# basketball_robot_connection_strip_2018.net
KiCad netlist of a schematic drawn in Altium Designer
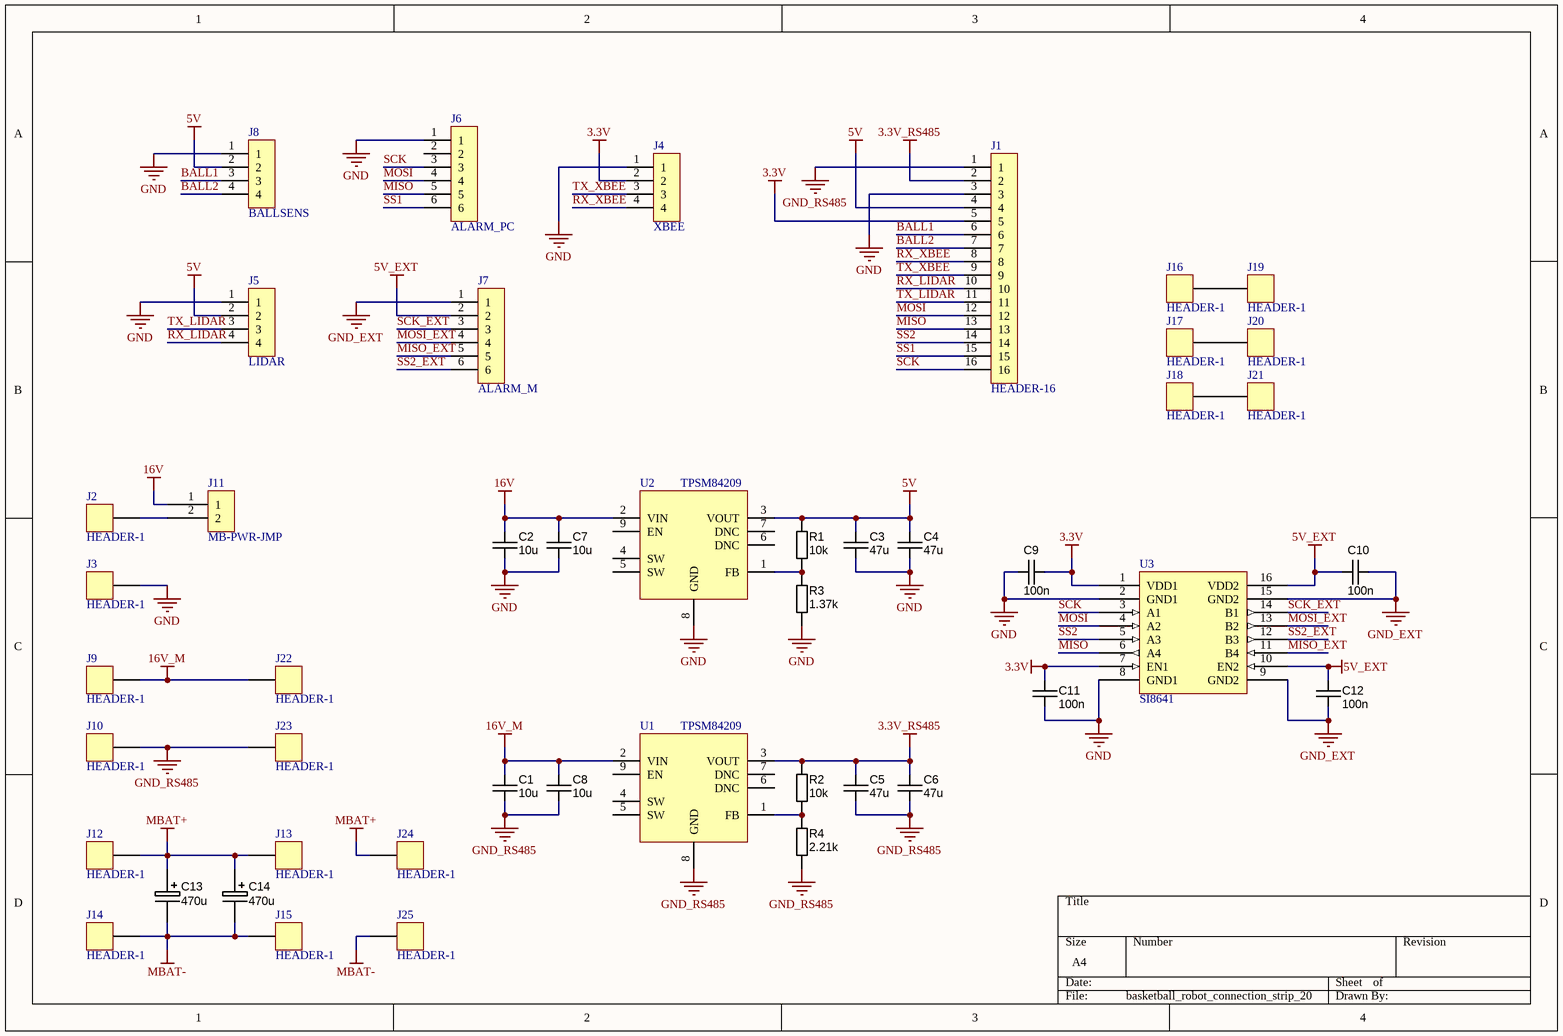
[diagram p0: basketball_robot_connection_strip_2018.SchDoc]

(export (version "E")
  (design (tool "Eeschema 10.0.6"))
  (components
    (comp (ref "C1")
      (value "10u")
      (footprint "CAPC3216X180N")
      (description "Capacitor SMD Cer 10uF 10% 10V X5R 1206")
      (fields (field (name "TOLERANCE") "±10%"))
      (libsource (lib "PBL - Capacitors") (part "CAPC_10u_1206_10V"))
    )
    (comp (ref "C2")
      (value "10u")
      (footprint "CAPC3216X180N")
      (description "Capacitor SMD Cer 10uF 10% 10V X5R 1206")
      (fields (field (name "TOLERANCE") "±10%"))
      (libsource (lib "PBL - Capacitors") (part "CAPC_10u_1206_10V"))
    )
    (comp (ref "C3")
      (value "47u")
      (footprint "CAPC3216X180N")
      (description "Capacitor SMD Cer 10uF 10% 10V X5R 1206")
      (fields (field (name "TOLERANCE") "±10%"))
      (libsource (lib "PBL - Capacitors") (part "CAPC_10u_1206_10V"))
    )
    (comp (ref "C4")
      (value "47u")
      (footprint "CAPC3216X180N")
      (description "Capacitor SMD Cer 10uF 10% 10V X5R 1206")
      (fields (field (name "TOLERANCE") "±10%"))
      (libsource (lib "PBL - Capacitors") (part "CAPC_10u_1206_10V"))
    )
    (comp (ref "C5")
      (value "47u")
      (footprint "CAPC3216X180N")
      (description "Capacitor SMD Cer 10uF 10% 10V X5R 1206")
      (fields (field (name "TOLERANCE") "±10%"))
      (libsource (lib "PBL - Capacitors") (part "CAPC_10u_1206_10V"))
    )
    (comp (ref "C6")
      (value "47u")
      (footprint "CAPC3216X180N")
      (description "Capacitor SMD Cer 10uF 10% 10V X5R 1206")
      (fields (field (name "TOLERANCE") "±10%"))
      (libsource (lib "PBL - Capacitors") (part "CAPC_10u_1206_10V"))
    )
    (comp (ref "C7")
      (value "10u")
      (footprint "CAPC3216X180N")
      (description "Capacitor SMD Cer 10uF 10% 10V X5R 1206")
      (fields (field (name "TOLERANCE") "±10%"))
      (libsource (lib "PBL - Capacitors") (part "CAPC_10u_1206_10V"))
    )
    (comp (ref "C8")
      (value "10u")
      (footprint "CAPC3216X180N")
      (description "Capacitor SMD Cer 10uF 10% 10V X5R 1206")
      (fields (field (name "TOLERANCE") "±10%"))
      (libsource (lib "PBL - Capacitors") (part "CAPC_10u_1206_10V"))
    )
    (comp (ref "C9")
      (value "100n")
      (footprint "CAPC1608X90N")
      (description "Capacitor SMD Cer 100nF 10% 50V X7R 0603")
      (fields (field (name "TOLERANCE") "±10%"))
      (libsource (lib "PBL - Capacitors") (part "CAPC_100n_0603_X7R_50V_10%"))
    )
    (comp (ref "C10")
      (value "100n")
      (footprint "CAPC1608X90N")
      (description "Capacitor SMD Cer 100nF 10% 50V X7R 0603")
      (fields (field (name "TOLERANCE") "±10%"))
      (libsource (lib "PBL - Capacitors") (part "CAPC_100n_0603_X7R_50V_10%"))
    )
    (comp (ref "C11")
      (value "100n")
      (footprint "CAPC1608X90N")
      (description "Capacitor SMD Cer 100nF 10% 50V X7R 0603")
      (fields (field (name "TOLERANCE") "±10%"))
      (libsource (lib "PBL - Capacitors") (part "CAPC_100n_0603_X7R_50V_10%"))
    )
    (comp (ref "C12")
      (value "100n")
      (footprint "CAPC1608X90N")
      (description "Capacitor SMD Cer 100nF 10% 50V X7R 0603")
      (fields (field (name "TOLERANCE") "±10%"))
      (libsource (lib "PBL - Capacitors") (part "CAPC_100n_0603_X7R_50V_10%"))
    )
    (comp (ref "C13")
      (value "470u")
      (footprint "CAPE10.0MM_Rad_10x14mm")
      (description "Capacitor THT Alum Elec 470uF 20% 16V")
      (fields (field (name "TOLERANCE") "±20%"))
      (libsource (lib "PBL - Capacitors") (part "CAPE_470u_16V_THT"))
    )
    (comp (ref "C14")
      (value "470u")
      (footprint "CAPE10.0MM_Rad_10x14mm")
      (description "Capacitor THT Alum Elec 470uF 20% 16V")
      (fields (field (name "TOLERANCE") "±20%"))
      (libsource (lib "PBL - Capacitors") (part "CAPE_470u_16V_THT"))
    )
    (comp (ref "J1")
      (value "HEADER-16")
      (footprint "MICRO-MATCH-MOB-16")
      (libsource (lib "connectors_micromatch") (part "HEADER-16"))
    )
    (comp (ref "J2")
      (value "HEADER-1")
      (footprint "2MM-BULLET-PLUG-VIA")
      (libsource (lib "connectors") (part "HEADER-1"))
    )
    (comp (ref "J3")
      (value "HEADER-1")
      (footprint "2MM-BULLET-PLUG-VIA")
      (libsource (lib "connectors") (part "HEADER-1"))
    )
    (comp (ref "J4")
      (value "XBEE")
      (footprint "MICRO-MATCH-FOB-04")
      (libsource (lib "connectors_micromatch") (part "HEADER-4"))
    )
    (comp (ref "J5")
      (value "LIDAR")
      (footprint "MICRO-MATCH-FOB-04")
      (libsource (lib "connectors_micromatch") (part "HEADER-4"))
    )
    (comp (ref "J6")
      (value "ALARM_PC")
      (footprint "MICRO-MATCH-MOB-06")
      (libsource (lib "connectors_micromatch") (part "HEADER-6"))
    )
    (comp (ref "J7")
      (value "ALARM_M")
      (footprint "MICRO-MATCH-MOB-06")
      (libsource (lib "connectors_micromatch") (part "HEADER-6"))
    )
    (comp (ref "J8")
      (value "BALLSENS")
      (footprint "MICRO-MATCH-FOB-04")
      (libsource (lib "connectors_micromatch") (part "HEADER-4"))
    )
    (comp (ref "J9")
      (value "HEADER-1")
      (footprint "POWER-PAD-4x3")
      (libsource (lib "connectors") (part "HEADER-1"))
    )
    (comp (ref "J10")
      (value "HEADER-1")
      (footprint "POWER-PAD-4x3")
      (libsource (lib "connectors") (part "HEADER-1"))
    )
    (comp (ref "J11")
      (value "MB-PWR-JMP")
      (footprint "PIN-HEADER-2")
      (libsource (lib "connectors") (part "HEADER-2"))
    )
    (comp (ref "J12")
      (value "HEADER-1")
      (footprint "2MM-BULLET-PLUG-VIA")
      (libsource (lib "connectors") (part "HEADER-1"))
    )
    (comp (ref "J13") (value "HEADER-1") (footprint "POWER-PAD-4x3") (libsource (lib "") (part "HEADER-1_1")))
    (comp (ref "J14")
      (value "HEADER-1")
      (footprint "2MM-BULLET-PLUG-VIA")
      (libsource (lib "connectors") (part "HEADER-1"))
    )
    (comp (ref "J15") (value "HEADER-1") (footprint "POWER-PAD-4x3") (libsource (lib "") (part "HEADER-1_1")))
    (comp (ref "J16")
      (value "HEADER-1")
      (footprint "2MM-BANANA-VIA")
      (libsource (lib "connectors") (part "HEADER-1"))
    )
    (comp (ref "J17")
      (value "HEADER-1")
      (footprint "2MM-BANANA-VIA")
      (libsource (lib "connectors") (part "HEADER-1"))
    )
    (comp (ref "J18")
      (value "HEADER-1")
      (footprint "2MM-BANANA-VIA")
      (libsource (lib "connectors") (part "HEADER-1"))
    )
    (comp (ref "J19") (value "HEADER-1") (footprint "POWER-PAD-4x3") (libsource (lib "") (part "HEADER-1_1")))
    (comp (ref "J20") (value "HEADER-1") (footprint "POWER-PAD-4x3") (libsource (lib "") (part "HEADER-1_1")))
    (comp (ref "J21") (value "HEADER-1") (footprint "POWER-PAD-4x3") (libsource (lib "") (part "HEADER-1_1")))
    (comp (ref "J22")
      (value "HEADER-1")
      (footprint "2MM-BULLET-PLUG-VIA")
      (libsource (lib "") (part "HEADER-1_1"))
    )
    (comp (ref "J23")
      (value "HEADER-1")
      (footprint "2MM-BULLET-PLUG-VIA")
      (libsource (lib "") (part "HEADER-1_1"))
    )
    (comp (ref "J24")
      (value "HEADER-1")
      (footprint "2MM-BULLET-PLUG-VIA")
      (libsource (lib "") (part "HEADER-1_1"))
    )
    (comp (ref "J25")
      (value "HEADER-1")
      (footprint "2MM-BULLET-PLUG-VIA")
      (libsource (lib "") (part "HEADER-1_1"))
    )
    (comp (ref "R1")
      (value "10k")
      (footprint "RESC1608X55N")
      (description "Resistor SMD chip 10k Ohm 0.1W 1% 0603")
      (fields (field (name "TOLERANCE") "±1%"))
      (libsource (lib "PBL - Resistors") (part "RES_10K_0603_1%"))
    )
    (comp (ref "R2")
      (value "10k")
      (footprint "RESC1608X55N")
      (description "Resistor SMD chip 10k Ohm 0.1W 1% 0603")
      (fields (field (name "TOLERANCE") "±1%"))
      (libsource (lib "PBL - Resistors") (part "RES_10K_0603_1%"))
    )
    (comp (ref "R3")
      (value "1.37k")
      (footprint "RESC1608X55N")
      (description "Resistor SMD chip 10k Ohm 0.1W 1% 0603")
      (fields (field (name "TOLERANCE") "±1%"))
      (libsource (lib "PBL - Resistors") (part "RES_10K_0603_1%"))
    )
    (comp (ref "R4")
      (value "2.21k")
      (footprint "RESC1608X55N")
      (description "Resistor SMD chip 10k Ohm 0.1W 1% 0603")
      (fields (field (name "TOLERANCE") "±1%"))
      (libsource (lib "PBL - Resistors") (part "RES_10K_0603_1%"))
    )
    (comp (ref "U1") (value "TPSM84209") (footprint "TPSM84209") (libsource (lib "power") (part "TPSM84209")))
    (comp (ref "U2") (value "TPSM84209") (footprint "TPSM84209") (libsource (lib "power") (part "TPSM84209")))
    (comp (ref "U3") (value "SI8641") (footprint "SOIC16") (libsource (lib "digital") (part "SI8641")))
  )
  (nets
    (net (code "1") (name "/BALL1") (class "Default")
      (node (ref "J1") (pin "6") (pinfunction "6_6") (pintype "passive"))
      (node (ref "J8") (pin "3") (pinfunction "3_3") (pintype "passive"))
    )
    (net (code "2") (name "/BALL2") (class "Default")
      (node (ref "J1") (pin "7") (pinfunction "7_7") (pintype "passive"))
      (node (ref "J8") (pin "4") (pinfunction "4_4") (pintype "passive"))
    )
    (net (code "3") (name "/MISO") (class "Default")
      (node (ref "J1") (pin "13") (pinfunction "13_13") (pintype "passive"))
      (node (ref "J6") (pin "5") (pinfunction "5_5") (pintype "passive"))
      (node (ref "U3") (pin "6") (pinfunction "A4_6") (pintype "output"))
    )
    (net (code "4") (name "/MISO_EXT") (class "Default")
      (node (ref "J7") (pin "5") (pinfunction "5_5") (pintype "passive"))
      (node (ref "U3") (pin "11") (pinfunction "B4_11") (pintype "input"))
    )
    (net (code "5") (name "/MOSI") (class "Default")
      (node (ref "J1") (pin "12") (pinfunction "12_12") (pintype "passive"))
      (node (ref "J6") (pin "4") (pinfunction "4_4") (pintype "passive"))
      (node (ref "U3") (pin "4") (pinfunction "A2_4") (pintype "input"))
    )
    (net (code "6") (name "/MOSI_EXT") (class "Default")
      (node (ref "J7") (pin "4") (pinfunction "4_4") (pintype "passive"))
      (node (ref "U3") (pin "13") (pinfunction "B2_13") (pintype "output"))
    )
    (net (code "7") (name "/RX_LIDAR") (class "Default")
      (node (ref "J1") (pin "10") (pinfunction "10_10") (pintype "passive"))
      (node (ref "J5") (pin "4") (pinfunction "4_4") (pintype "passive"))
    )
    (net (code "8") (name "/RX_XBEE") (class "Default")
      (node (ref "J1") (pin "8") (pinfunction "8_8") (pintype "passive"))
      (node (ref "J4") (pin "4") (pinfunction "4_4") (pintype "passive"))
    )
    (net (code "9") (name "/SCK") (class "Default")
      (node (ref "J1") (pin "16") (pinfunction "16_16") (pintype "passive"))
      (node (ref "J6") (pin "3") (pinfunction "3_3") (pintype "passive"))
      (node (ref "U3") (pin "3") (pinfunction "A1_3") (pintype "input"))
    )
    (net (code "10") (name "/SCK_EXT") (class "Default")
      (node (ref "J7") (pin "3") (pinfunction "3_3") (pintype "passive"))
      (node (ref "U3") (pin "14") (pinfunction "B1_14") (pintype "output"))
    )
    (net (code "11") (name "/SS1") (class "Default")
      (node (ref "J1") (pin "15") (pinfunction "15_15") (pintype "passive"))
      (node (ref "J6") (pin "6") (pinfunction "6_6") (pintype "passive"))
    )
    (net (code "12") (name "/SS2") (class "Default")
      (node (ref "J1") (pin "14") (pinfunction "14_14") (pintype "passive"))
      (node (ref "U3") (pin "5") (pinfunction "A3_5") (pintype "input"))
    )
    (net (code "13") (name "/SS2_EXT") (class "Default")
      (node (ref "J7") (pin "6") (pinfunction "6_6") (pintype "passive"))
      (node (ref "U3") (pin "12") (pinfunction "B3_12") (pintype "output"))
    )
    (net (code "14") (name "/TX_LIDAR") (class "Default")
      (node (ref "J1") (pin "11") (pinfunction "11_11") (pintype "passive"))
      (node (ref "J5") (pin "3") (pinfunction "3_3") (pintype "passive"))
    )
    (net (code "15") (name "/TX_XBEE") (class "Default")
      (node (ref "J1") (pin "9") (pinfunction "9_9") (pintype "passive"))
      (node (ref "J4") (pin "3") (pinfunction "3_3") (pintype "passive"))
    )
    (net (code "16") (name "3.3V") (class "Default")
      (node (ref "C11") (pin "2") (pintype "passive"))
      (node (ref "C9") (pin "1") (pintype "passive"))
      (node (ref "J1") (pin "5") (pinfunction "5_5") (pintype "passive"))
      (node (ref "J4") (pin "2") (pinfunction "2_2") (pintype "passive"))
      (node (ref "U3") (pin "1") (pinfunction "VDD1_1") (pintype "power_in"))
      (node (ref "U3") (pin "7") (pinfunction "EN1_7") (pintype "input"))
    )
    (net (code "17") (name "3.3V_RS485") (class "Default")
      (node (ref "C5") (pin "1") (pintype "passive"))
      (node (ref "C6") (pin "1") (pintype "passive"))
      (node (ref "J1") (pin "2") (pinfunction "2_2") (pintype "passive"))
      (node (ref "R2") (pin "1") (pinfunction "1_1") (pintype "passive"))
      (node (ref "U1") (pin "3") (pinfunction "VOUT_3") (pintype "passive"))
    )
    (net (code "18") (name "5V") (class "Default")
      (node (ref "C3") (pin "1") (pintype "passive"))
      (node (ref "C4") (pin "1") (pintype "passive"))
      (node (ref "J1") (pin "4") (pinfunction "4_4") (pintype "passive"))
      (node (ref "J5") (pin "2") (pinfunction "2_2") (pintype "passive"))
      (node (ref "J8") (pin "2") (pinfunction "2_2") (pintype "passive"))
      (node (ref "R1") (pin "1") (pinfunction "1_1") (pintype "passive"))
      (node (ref "U2") (pin "3") (pinfunction "VOUT_3") (pintype "passive"))
    )
    (net (code "19") (name "5V_EXT") (class "Default")
      (node (ref "C10") (pin "1") (pintype "passive"))
      (node (ref "C12") (pin "2") (pintype "passive"))
      (node (ref "J7") (pin "2") (pinfunction "2_2") (pintype "passive"))
      (node (ref "U3") (pin "10") (pinfunction "EN2_10") (pintype "input"))
      (node (ref "U3") (pin "16") (pinfunction "VDD2_16") (pintype "power_in"))
    )
    (net (code "20") (name "16V") (class "Default")
      (node (ref "C2") (pin "1") (pintype "passive"))
      (node (ref "C7") (pin "1") (pintype "passive"))
      (node (ref "J11") (pin "1") (pinfunction "1_1") (pintype "passive"))
      (node (ref "U2") (pin "2") (pinfunction "VIN_2") (pintype "passive"))
    )
    (net (code "21") (name "16V_M") (class "Default")
      (node (ref "C1") (pin "1") (pintype "passive"))
      (node (ref "C8") (pin "1") (pintype "passive"))
      (node (ref "J22") (pin "1") (pinfunction "1_1") (pintype "passive"))
      (node (ref "J9") (pin "1") (pinfunction "1_1") (pintype "passive"))
      (node (ref "U1") (pin "2") (pinfunction "VIN_2") (pintype "passive"))
    )
    (net (code "22") (name "GND") (class "Default")
      (node (ref "C11") (pin "1") (pintype "passive"))
      (node (ref "C2") (pin "2") (pintype "passive"))
      (node (ref "C3") (pin "2") (pintype "passive"))
      (node (ref "C4") (pin "2") (pintype "passive"))
      (node (ref "C7") (pin "2") (pintype "passive"))
      (node (ref "C9") (pin "2") (pintype "passive"))
      (node (ref "J1") (pin "3") (pinfunction "3_3") (pintype "passive"))
      (node (ref "J3") (pin "1") (pinfunction "1_1") (pintype "passive"))
      (node (ref "J4") (pin "1") (pinfunction "1_1") (pintype "passive"))
      (node (ref "J5") (pin "1") (pinfunction "1_1") (pintype "passive"))
      (node (ref "J6") (pin "1") (pinfunction "1_1") (pintype "passive"))
      (node (ref "J8") (pin "1") (pinfunction "1_1") (pintype "passive"))
      (node (ref "R3") (pin "2") (pinfunction "2_2") (pintype "passive"))
      (node (ref "U2") (pin "8") (pinfunction "GND_8") (pintype "passive"))
      (node (ref "U3") (pin "2") (pinfunction "GND1_2") (pintype "power_in"))
      (node (ref "U3") (pin "8") (pinfunction "GND1_8") (pintype "power_in"))
    )
    (net (code "23") (name "GND_EXT") (class "Default")
      (node (ref "C10") (pin "2") (pintype "passive"))
      (node (ref "C12") (pin "1") (pintype "passive"))
      (node (ref "J7") (pin "1") (pinfunction "1_1") (pintype "passive"))
      (node (ref "U3") (pin "15") (pinfunction "GND2_15") (pintype "power_in"))
      (node (ref "U3") (pin "9") (pinfunction "GND2_9") (pintype "power_in"))
    )
    (net (code "24") (name "GND_RS485") (class "Default")
      (node (ref "C1") (pin "2") (pintype "passive"))
      (node (ref "C5") (pin "2") (pintype "passive"))
      (node (ref "C6") (pin "2") (pintype "passive"))
      (node (ref "C8") (pin "2") (pintype "passive"))
      (node (ref "J1") (pin "1") (pinfunction "1_1") (pintype "passive"))
      (node (ref "J10") (pin "1") (pinfunction "1_1") (pintype "passive"))
      (node (ref "J23") (pin "1") (pinfunction "1_1") (pintype "passive"))
      (node (ref "R4") (pin "2") (pinfunction "2_2") (pintype "passive"))
      (node (ref "U1") (pin "8") (pinfunction "GND_8") (pintype "passive"))
    )
    (net (code "25") (name "MBAT+") (class "Default")
      (node (ref "C13") (pin "1") (pintype "passive"))
      (node (ref "C14") (pin "1") (pintype "passive"))
      (node (ref "J12") (pin "1") (pinfunction "1_1") (pintype "passive"))
      (node (ref "J13") (pin "1") (pinfunction "1_1") (pintype "passive"))
      (node (ref "J24") (pin "1") (pinfunction "1_1") (pintype "passive"))
    )
    (net (code "26") (name "MBAT-") (class "Default")
      (node (ref "C13") (pin "2") (pintype "passive"))
      (node (ref "C14") (pin "2") (pintype "passive"))
      (node (ref "J14") (pin "1") (pinfunction "1_1") (pintype "passive"))
      (node (ref "J15") (pin "1") (pinfunction "1_1") (pintype "passive"))
      (node (ref "J25") (pin "1") (pinfunction "1_1") (pintype "passive"))
    )
    (net (code "27") (name "Net-(J11-Pad2)") (class "Default")
      (node (ref "J11") (pin "2") (pinfunction "2_2") (pintype "passive"))
      (node (ref "J2") (pin "1") (pinfunction "1_1") (pintype "passive"))
    )
    (net (code "28") (name "Net-(J16-Pad1)") (class "Default")
      (node (ref "J16") (pin "1") (pinfunction "1_1") (pintype "passive"))
      (node (ref "J19") (pin "1") (pinfunction "1_1") (pintype "passive"))
    )
    (net (code "29") (name "Net-(J17-Pad1)") (class "Default")
      (node (ref "J17") (pin "1") (pinfunction "1_1") (pintype "passive"))
      (node (ref "J20") (pin "1") (pinfunction "1_1") (pintype "passive"))
    )
    (net (code "30") (name "Net-(J18-Pad1)") (class "Default")
      (node (ref "J18") (pin "1") (pinfunction "1_1") (pintype "passive"))
      (node (ref "J21") (pin "1") (pinfunction "1_1") (pintype "passive"))
    )
    (net (code "31") (name "Net-(U1-FB)") (class "Default")
      (node (ref "R2") (pin "2") (pinfunction "2_2") (pintype "passive"))
      (node (ref "R4") (pin "1") (pinfunction "1_1") (pintype "passive"))
      (node (ref "U1") (pin "1") (pinfunction "FB_1") (pintype "passive"))
    )
    (net (code "32") (name "Net-(U2-FB)") (class "Default")
      (node (ref "R1") (pin "2") (pinfunction "2_2") (pintype "passive"))
      (node (ref "R3") (pin "1") (pinfunction "1_1") (pintype "passive"))
      (node (ref "U2") (pin "1") (pinfunction "FB_1") (pintype "passive"))
    )
    (net (code "33") (name "unconnected-(J6-Pad2)") (class "Default")
      (node (ref "J6") (pin "2") (pinfunction "2_2") (pintype "passive"))
    )
    (net (code "34") (name "unconnected-(U1-DNC-Pad6)") (class "Default")
      (node (ref "U1") (pin "6") (pinfunction "DNC_6") (pintype "passive"))
    )
    (net (code "35") (name "unconnected-(U1-DNC-Pad7)") (class "Default")
      (node (ref "U1") (pin "7") (pinfunction "DNC_7") (pintype "passive"))
    )
    (net (code "36") (name "unconnected-(U1-EN-Pad9)") (class "Default")
      (node (ref "U1") (pin "9") (pinfunction "EN_9") (pintype "passive"))
    )
    (net (code "37") (name "unconnected-(U1-SW-Pad4)") (class "Default")
      (node (ref "U1") (pin "4") (pinfunction "SW_4") (pintype "passive"))
    )
    (net (code "38") (name "unconnected-(U1-SW-Pad5)") (class "Default")
      (node (ref "U1") (pin "5") (pinfunction "SW_5") (pintype "passive"))
    )
    (net (code "39") (name "unconnected-(U2-DNC-Pad6)") (class "Default")
      (node (ref "U2") (pin "6") (pinfunction "DNC_6") (pintype "passive"))
    )
    (net (code "40") (name "unconnected-(U2-DNC-Pad7)") (class "Default")
      (node (ref "U2") (pin "7") (pinfunction "DNC_7") (pintype "passive"))
    )
    (net (code "41") (name "unconnected-(U2-EN-Pad9)") (class "Default")
      (node (ref "U2") (pin "9") (pinfunction "EN_9") (pintype "passive"))
    )
    (net (code "42") (name "unconnected-(U2-SW-Pad4)") (class "Default")
      (node (ref "U2") (pin "4") (pinfunction "SW_4") (pintype "passive"))
    )
    (net (code "43") (name "unconnected-(U2-SW-Pad5)") (class "Default")
      (node (ref "U2") (pin "5") (pinfunction "SW_5") (pintype "passive"))
    )
  )
)
